# 2016_CARTE_PUISSANCE.net
KiCad netlist of a schematic drawn in Altium Designer
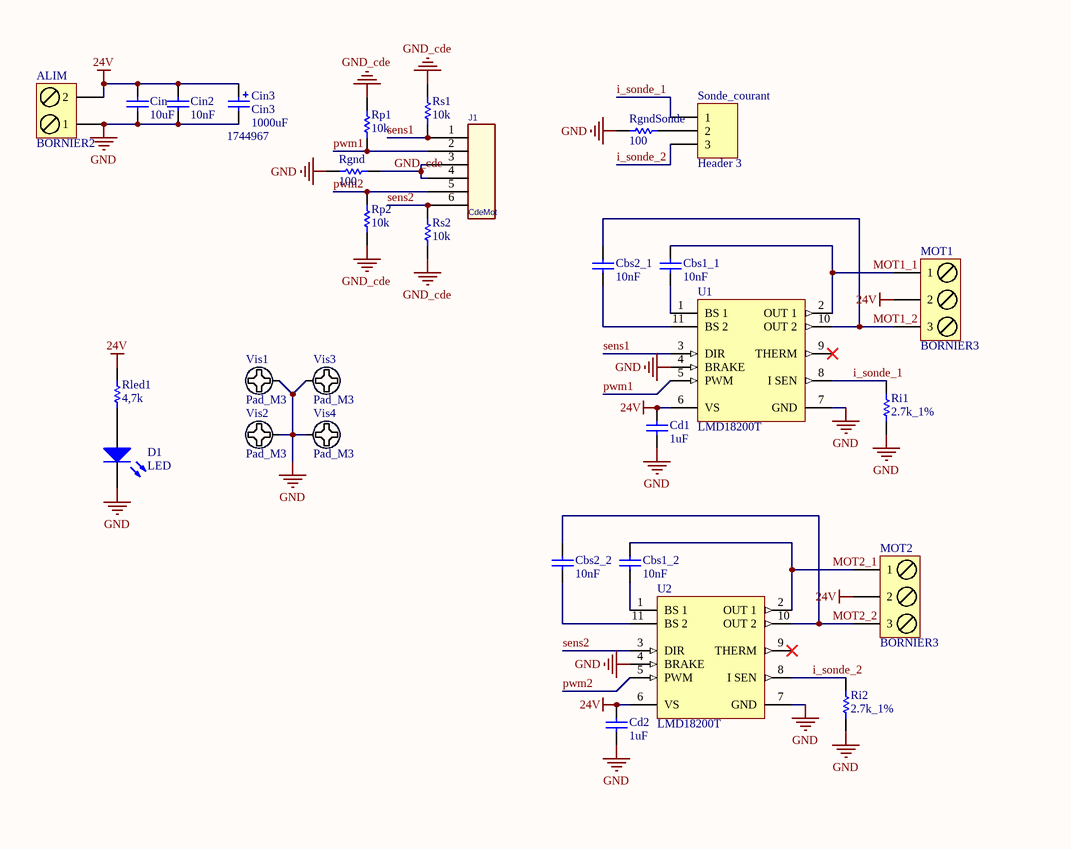
[diagram p0: 2016_CARTE_PUISSANCE.SchDoc, left]
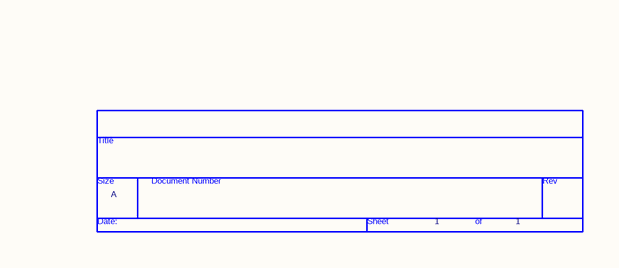
[diagram p1: 2016_CARTE_PUISSANCE.SchDoc, right]

(export (version "E")
  (design (tool "Eeschema 10.0.6"))
  (components
    (comp (ref "*")
      (value "TitleBlock0")
      (fields (field (name "PAGE COUNT") "1") (field (name "PAGE NUMBER") "1") (field (name "PAGE SIZE") "A"))
      (libsource (lib "*") (part "TitleBlock0"))
    )
    (comp (ref "ALIM")
      (value "BORNIER2")
      (footprint "BORNIER2")
      (description "Terminal blocks, 2 pins, pitch=5mm")
      (libsource (lib "Robot2010") (part "BORNIER2"))
    )
    (comp (ref "Cbs1_1")
      (value "10nF")
      (footprint "C0805_N")
      (description "Capacitor")
      (fields (field (name "PUBLISHER") "Altium Limited"))
      (libsource (lib "DG_Condensateur") (part "Capacitor"))
    )
    (comp (ref "Cbs1_2")
      (value "10nF")
      (footprint "C0805_N")
      (description "Capacitor")
      (fields (field (name "PUBLISHER") "Altium Limited"))
      (libsource (lib "DG_Condensateur") (part "Capacitor"))
    )
    (comp (ref "Cbs2_1")
      (value "10nF")
      (footprint "C0805_N")
      (description "Capacitor")
      (fields (field (name "PUBLISHER") "Altium Limited"))
      (libsource (lib "DG_Condensateur") (part "Capacitor"))
    )
    (comp (ref "Cbs2_2")
      (value "10nF")
      (footprint "C0805_N")
      (description "Capacitor")
      (fields (field (name "PUBLISHER") "Altium Limited"))
      (libsource (lib "DG_Condensateur") (part "Capacitor"))
    )
    (comp (ref "Cd1")
      (value "1uF")
      (footprint "C1206_N")
      (description "Capacitor")
      (fields (field (name "PUBLISHER") "Altium Limited"))
      (libsource (lib "DG_Condensateur") (part "Capacitor"))
    )
    (comp (ref "Cd2")
      (value "1uF")
      (footprint "C1206_N")
      (description "Capacitor")
      (fields (field (name "PUBLISHER") "Altium Limited"))
      (libsource (lib "DG_Condensateur") (part "Capacitor"))
    )
    (comp (ref "Cin")
      (value "10uF")
      (footprint "C1206_N")
      (description "Capacitor")
      (fields (field (name "PUBLISHER") "Altium Limited"))
      (libsource (lib "DG_Condensateur") (part "Capacitor"))
    )
    (comp (ref "Cin2")
      (value "10nF")
      (footprint "C0805_N")
      (description "Capacitor")
      (fields (field (name "PUBLISHER") "Altium Limited"))
      (libsource (lib "DG_Condensateur") (part "Capacitor"))
    )
    (comp (ref "Cin3")
      (value "Cin3")
      (footprint "COND_POL_RAD_5.08B")
      (description "Polarized Capacitor")
      (fields
        (field (name "ALTIUM_VALUE") "1000uF")
        (field (name "FAR") "1744967")
        (field (name "PUBLISHER") "Altium Limited")
      )
      (libsource (lib "Robot2010") (part "CONDENSATEUR_POLARISE"))
    )
    (comp (ref "D1")
      (value "LED")
      (footprint "LED_3mm")
      (description "Typical LED")
      (fields (field (name "PUBLISHER") "Altium Limited"))
      (libsource (lib "DG_LED") (part "LED"))
    )
    (comp (ref "J1") (value "CdeMot") (footprint "RJ11_6/6") (libsource (lib "*") (part "CONNECTEUR_RJ12")))
    (comp (ref "MOT1")
      (value "BORNIER3")
      (footprint "BORNIER3")
      (description "Terminal blocks, 2 pins, pitch=5mm")
      (libsource (lib "Robot2010") (part "BORNIER3"))
    )
    (comp (ref "MOT2")
      (value "BORNIER3")
      (footprint "BORNIER3")
      (description "Terminal blocks, 2 pins, pitch=5mm")
      (libsource (lib "Robot2010") (part "BORNIER3"))
    )
    (comp (ref "Rgnd")
      (value "100")
      (footprint "R1206_N")
      (description "Resistor")
      (fields (field (name "PUBLISHER") "Altium Limited"))
      (libsource (lib "DG_Resistance") (part "Resistor"))
    )
    (comp (ref "RgndSonde")
      (value "100")
      (footprint "R1206_N")
      (description "Resistor")
      (fields (field (name "PUBLISHER") "Altium Limited"))
      (libsource (lib "DG_Resistance") (part "Resistor"))
    )
    (comp (ref "Ri1")
      (value "2.7k_1%")
      (footprint "R1206_N")
      (description "Resistor")
      (fields (field (name "PUBLISHER") "Altium Limited"))
      (libsource (lib "DG_Resistance") (part "Resistor"))
    )
    (comp (ref "Ri2")
      (value "2.7k_1%")
      (footprint "R1206_N")
      (description "Resistor")
      (fields (field (name "PUBLISHER") "Altium Limited"))
      (libsource (lib "DG_Resistance") (part "Resistor"))
    )
    (comp (ref "Rled1")
      (value "4,7k")
      (footprint "R1206_N")
      (description "Resistor")
      (fields (field (name "PUBLISHER") "Altium Limited"))
      (libsource (lib "DG_Resistance") (part "Resistor"))
    )
    (comp (ref "Rp1")
      (value "10k")
      (footprint "R1206_N")
      (description "Resistor")
      (fields (field (name "PUBLISHER") "Altium Limited"))
      (libsource (lib "DG_Resistance") (part "Resistor"))
    )
    (comp (ref "Rp2")
      (value "10k")
      (footprint "R1206_N")
      (description "Resistor")
      (fields (field (name "PUBLISHER") "Altium Limited"))
      (libsource (lib "DG_Resistance") (part "Resistor"))
    )
    (comp (ref "Rs1")
      (value "10k")
      (footprint "R1206_N")
      (description "Resistor")
      (fields (field (name "PUBLISHER") "Altium Limited"))
      (libsource (lib "DG_Resistance") (part "Resistor"))
    )
    (comp (ref "Rs2")
      (value "10k")
      (footprint "R1206_N")
      (description "Resistor")
      (fields (field (name "PUBLISHER") "Altium Limited"))
      (libsource (lib "DG_Resistance") (part "Resistor"))
    )
    (comp (ref "Sonde_courant")
      (value "Header 3")
      (footprint "HDR1X3")
      (description "Header, 3-Pin")
      (fields (field (name "PUBLISHER") "Altium Limited"))
      (libsource (lib "DG_Connecteur") (part "Header 3"))
    )
    (comp (ref "U1")
      (value "LMD18200T")
      (footprint "TA11B")
      (description "3A, 55V H-Bridge")
      (fields
        (field (name "MANUFACTURER") "National Semiconductor")
        (field (name "DIGIKEYPARTNUMBER") "LMD18200T-ND")
        (field (name "PUBLISHER") "Altium Limited")
      )
      (libsource (lib "NSC MiscPower") (part "LMD18200T"))
    )
    (comp (ref "U2")
      (value "LMD18200T")
      (footprint "TA11B")
      (description "3A, 55V H-Bridge")
      (fields
        (field (name "MANUFACTURER") "National Semiconductor")
        (field (name "DIGIKEYPARTNUMBER") "LMD18200T-ND")
        (field (name "PUBLISHER") "Altium Limited")
      )
      (libsource (lib "NSC MiscPower") (part "LMD18200T"))
    )
    (comp (ref "Vis1")
      (value "Pad_M3")
      (footprint "M3x6mm")
      (description "Vis M3 X 6mm _TORX_Tête 6mm")
      (fields (field (name "PUBLISHER") "Damien Guitton"))
      (libsource (lib "DG_Mecanique") (part "Vis M3 X 6mm _TORX_Tête 6mm"))
    )
    (comp (ref "Vis2")
      (value "Pad_M3")
      (footprint "M3x6mm")
      (description "Vis M3 X 6mm _TORX_Tête 6mm")
      (fields (field (name "PUBLISHER") "Damien Guitton"))
      (libsource (lib "DG_Mecanique") (part "Vis M3 X 6mm _TORX_Tête 6mm"))
    )
    (comp (ref "Vis3")
      (value "Pad_M3")
      (footprint "M3x6mm")
      (description "Vis M3 X 6mm _TORX_Tête 6mm")
      (fields (field (name "PUBLISHER") "Damien Guitton"))
      (libsource (lib "DG_Mecanique") (part "Vis M3 X 6mm _TORX_Tête 6mm"))
    )
    (comp (ref "Vis4")
      (value "Pad_M3")
      (footprint "M3x6mm")
      (description "Vis M3 X 6mm _TORX_Tête 6mm")
      (fields (field (name "PUBLISHER") "Damien Guitton"))
      (libsource (lib "DG_Mecanique") (part "Vis M3 X 6mm _TORX_Tête 6mm"))
    )
  )
  (nets
    (net (code "1") (name "/MOT1_1") (class "Default")
      (node (ref "Cbs1_1") (pin "2") (pinfunction "2_2") (pintype "passive"))
      (node (ref "MOT1") (pin "1") (pinfunction "1_1") (pintype "passive"))
      (node (ref "U1") (pin "2") (pinfunction "OUT_1_2") (pintype "output"))
    )
    (net (code "2") (name "/MOT1_2") (class "Default")
      (node (ref "Cbs2_1") (pin "2") (pinfunction "2_2") (pintype "passive"))
      (node (ref "MOT1") (pin "3") (pinfunction "3_3") (pintype "passive"))
      (node (ref "U1") (pin "10") (pinfunction "OUT_2_10") (pintype "output"))
    )
    (net (code "3") (name "/MOT2_1") (class "Default")
      (node (ref "Cbs1_2") (pin "2") (pinfunction "2_2") (pintype "passive"))
      (node (ref "MOT2") (pin "1") (pinfunction "1_1") (pintype "passive"))
      (node (ref "U2") (pin "2") (pinfunction "OUT_1_2") (pintype "output"))
    )
    (net (code "4") (name "/MOT2_2") (class "Default")
      (node (ref "Cbs2_2") (pin "2") (pinfunction "2_2") (pintype "passive"))
      (node (ref "MOT2") (pin "3") (pinfunction "3_3") (pintype "passive"))
      (node (ref "U2") (pin "10") (pinfunction "OUT_2_10") (pintype "output"))
    )
    (net (code "5") (name "/i_sonde_1") (class "Default")
      (node (ref "Ri1") (pin "1") (pinfunction "1_1") (pintype "passive"))
      (node (ref "Sonde_courant") (pin "1") (pinfunction "1_1") (pintype "passive"))
      (node (ref "U1") (pin "8") (pinfunction "I_SEN_8") (pintype "output"))
    )
    (net (code "6") (name "/i_sonde_2") (class "Default")
      (node (ref "Ri2") (pin "1") (pinfunction "1_1") (pintype "passive"))
      (node (ref "Sonde_courant") (pin "3") (pinfunction "3_3") (pintype "passive"))
      (node (ref "U2") (pin "8") (pinfunction "I_SEN_8") (pintype "output"))
    )
    (net (code "7") (name "/pwm1") (class "Default")
      (node (ref "J1") (pin "2") (pinfunction "2_2") (pintype "passive"))
      (node (ref "Rp1") (pin "1") (pinfunction "1_1") (pintype "passive"))
      (node (ref "U1") (pin "5") (pinfunction "PWM_5") (pintype "input"))
    )
    (net (code "8") (name "/pwm2") (class "Default")
      (node (ref "J1") (pin "5") (pinfunction "5_5") (pintype "passive"))
      (node (ref "Rp2") (pin "2") (pinfunction "2_2") (pintype "passive"))
      (node (ref "U2") (pin "5") (pinfunction "PWM_5") (pintype "input"))
    )
    (net (code "9") (name "/sens1") (class "Default")
      (node (ref "J1") (pin "1") (pinfunction "1_1") (pintype "passive"))
      (node (ref "Rs1") (pin "1") (pinfunction "1_1") (pintype "passive"))
      (node (ref "U1") (pin "3") (pinfunction "DIR_3") (pintype "input"))
    )
    (net (code "10") (name "/sens2") (class "Default")
      (node (ref "J1") (pin "6") (pinfunction "6_6") (pintype "passive"))
      (node (ref "Rs2") (pin "2") (pinfunction "2_2") (pintype "passive"))
      (node (ref "U2") (pin "3") (pinfunction "DIR_3") (pintype "input"))
    )
    (net (code "11") (name "24V") (class "Default")
      (node (ref "ALIM") (pin "2") (pinfunction "2_2") (pintype "passive"))
      (node (ref "Cd1") (pin "1") (pinfunction "1_1") (pintype "passive"))
      (node (ref "Cd2") (pin "1") (pinfunction "1_1") (pintype "passive"))
      (node (ref "Cin") (pin "2") (pinfunction "2_2") (pintype "passive"))
      (node (ref "Cin2") (pin "2") (pinfunction "2_2") (pintype "passive"))
      (node (ref "Cin3") (pin "1") (pinfunction "1_1") (pintype "passive"))
      (node (ref "MOT1") (pin "2") (pinfunction "2_2") (pintype "passive"))
      (node (ref "MOT2") (pin "2") (pinfunction "2_2") (pintype "passive"))
      (node (ref "Rled1") (pin "2") (pinfunction "2_2") (pintype "passive"))
      (node (ref "U1") (pin "6") (pinfunction "VS_6") (pintype "power_in"))
      (node (ref "U2") (pin "6") (pinfunction "VS_6") (pintype "power_in"))
    )
    (net (code "12") (name "GND") (class "Default")
      (node (ref "ALIM") (pin "1") (pinfunction "1_1") (pintype "passive"))
      (node (ref "Cd1") (pin "2") (pinfunction "2_2") (pintype "passive"))
      (node (ref "Cd2") (pin "2") (pinfunction "2_2") (pintype "passive"))
      (node (ref "Cin") (pin "1") (pinfunction "1_1") (pintype "passive"))
      (node (ref "Cin2") (pin "1") (pinfunction "1_1") (pintype "passive"))
      (node (ref "Cin3") (pin "2") (pinfunction "2_2") (pintype "passive"))
      (node (ref "D1") (pin "2") (pinfunction "2_2") (pintype "passive"))
      (node (ref "Rgnd") (pin "2") (pinfunction "2_2") (pintype "passive"))
      (node (ref "RgndSonde") (pin "2") (pinfunction "2_2") (pintype "passive"))
      (node (ref "Ri1") (pin "2") (pinfunction "2_2") (pintype "passive"))
      (node (ref "Ri2") (pin "2") (pinfunction "2_2") (pintype "passive"))
      (node (ref "U1") (pin "4") (pinfunction "BRAKE_4") (pintype "input"))
      (node (ref "U1") (pin "7") (pinfunction "GND_7") (pintype "power_in"))
      (node (ref "U2") (pin "4") (pinfunction "BRAKE_4") (pintype "input"))
      (node (ref "U2") (pin "7") (pinfunction "GND_7") (pintype "power_in"))
      (node (ref "Vis1") (pin "1") (pinfunction "1_1") (pintype "passive"))
      (node (ref "Vis2") (pin "1") (pinfunction "1_1") (pintype "passive"))
      (node (ref "Vis3") (pin "1") (pinfunction "1_1") (pintype "passive"))
      (node (ref "Vis4") (pin "1") (pinfunction "1_1") (pintype "passive"))
    )
    (net (code "13") (name "GND_cde") (class "Default")
      (node (ref "J1") (pin "3") (pinfunction "3_3") (pintype "passive"))
      (node (ref "J1") (pin "4") (pinfunction "4_4") (pintype "passive"))
      (node (ref "Rgnd") (pin "1") (pinfunction "1_1") (pintype "passive"))
      (node (ref "Rp1") (pin "2") (pinfunction "2_2") (pintype "passive"))
      (node (ref "Rp2") (pin "1") (pinfunction "1_1") (pintype "passive"))
      (node (ref "Rs1") (pin "2") (pinfunction "2_2") (pintype "passive"))
      (node (ref "Rs2") (pin "1") (pinfunction "1_1") (pintype "passive"))
    )
    (net (code "14") (name "Net-(D1-Pad1)") (class "Default")
      (node (ref "D1") (pin "1") (pinfunction "1_1") (pintype "passive"))
      (node (ref "Rled1") (pin "1") (pinfunction "1_1") (pintype "passive"))
    )
    (net (code "15") (name "Net-(RgndSonde-Pad1)") (class "Default")
      (node (ref "RgndSonde") (pin "1") (pinfunction "1_1") (pintype "passive"))
      (node (ref "Sonde_courant") (pin "2") (pinfunction "2_2") (pintype "passive"))
    )
    (net (code "16") (name "Net-(U1-BS_1)") (class "Default")
      (node (ref "Cbs1_1") (pin "1") (pinfunction "1_1") (pintype "passive"))
      (node (ref "U1") (pin "1") (pinfunction "BS_1_1") (pintype "passive"))
    )
    (net (code "17") (name "Net-(U1-BS_2)") (class "Default")
      (node (ref "Cbs2_1") (pin "1") (pinfunction "1_1") (pintype "passive"))
      (node (ref "U1") (pin "11") (pinfunction "BS_2_11") (pintype "passive"))
    )
    (net (code "18") (name "Net-(U2-BS_1)") (class "Default")
      (node (ref "Cbs1_2") (pin "1") (pinfunction "1_1") (pintype "passive"))
      (node (ref "U2") (pin "1") (pinfunction "BS_1_1") (pintype "passive"))
    )
    (net (code "19") (name "Net-(U2-BS_2)") (class "Default")
      (node (ref "Cbs2_2") (pin "1") (pinfunction "1_1") (pintype "passive"))
      (node (ref "U2") (pin "11") (pinfunction "BS_2_11") (pintype "passive"))
    )
    (net (code "20") (name "unconnected-(U1-THERM-Pad9)") (class "Default")
      (node (ref "U1") (pin "9") (pinfunction "THERM_9") (pintype "output+no_connect"))
    )
    (net (code "21") (name "unconnected-(U2-THERM-Pad9)") (class "Default")
      (node (ref "U2") (pin "9") (pinfunction "THERM_9") (pintype "output+no_connect"))
    )
  )
)
